# pokey-switch-board.net
KiCad netlist of a schematic drawn in Altium Designer
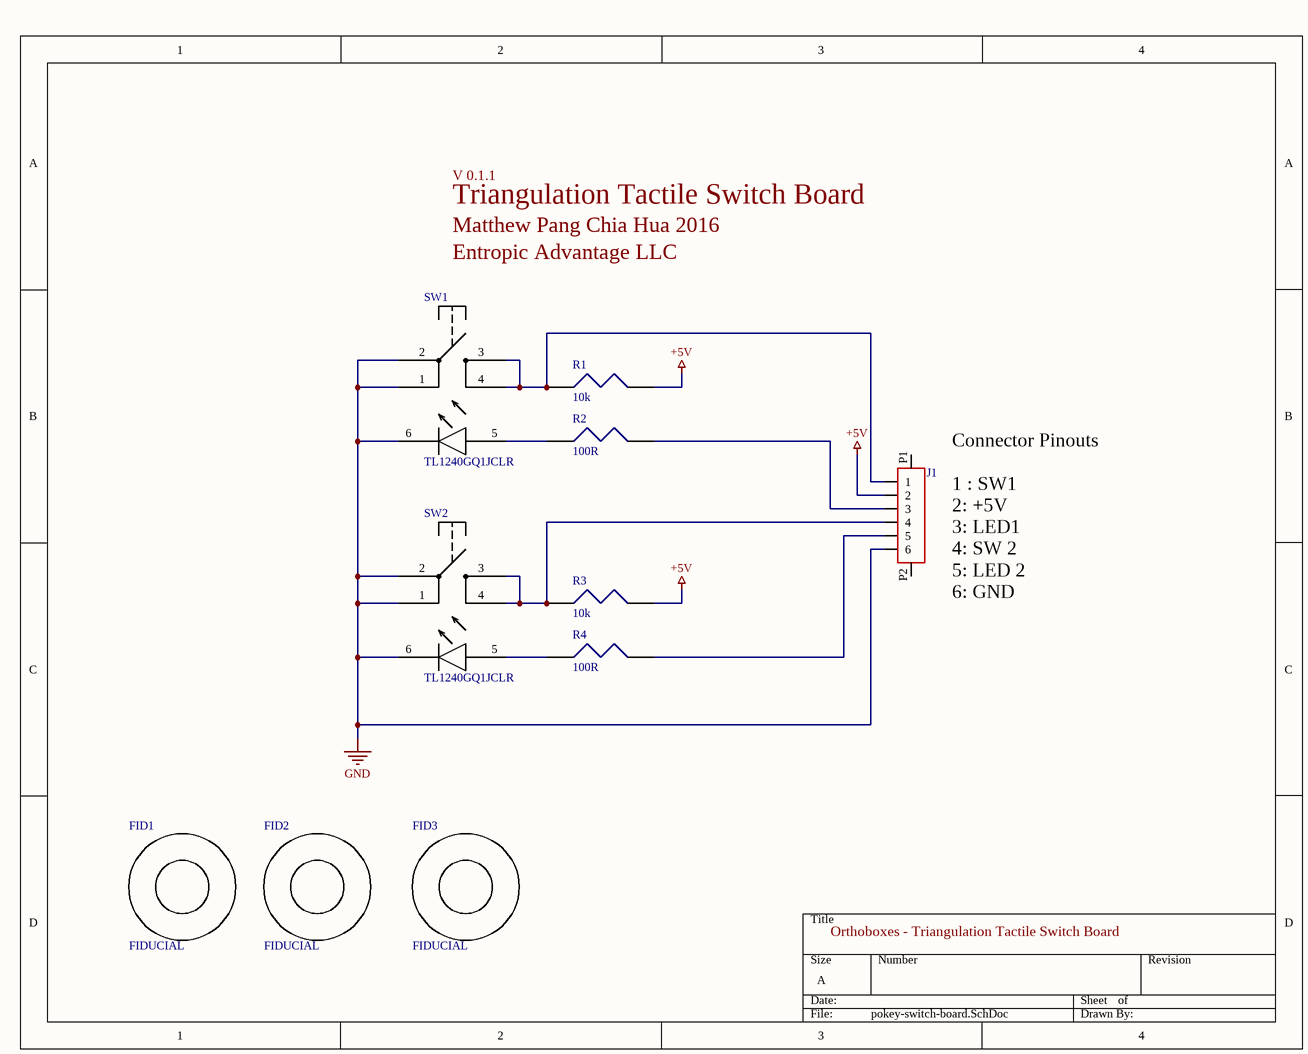
[diagram p0: pokey-switch-board.SchDoc]

(export (version "E")
  (design (tool "Eeschema 10.0.6"))
  (components
    (comp (ref "FID1")
      (value "FIDUCIAL")
      (footprint "pokey-switch-board:FID")
      (libsource (lib "pokey-switch-board") (part "Fiducial 1"))
    )
    (comp (ref "FID2")
      (value "FIDUCIAL")
      (footprint "pokey-switch-board:FID")
      (libsource (lib "pokey-switch-board") (part "Fiducial 1"))
    )
    (comp (ref "FID3")
      (value "FIDUCIAL")
      (footprint "pokey-switch-board:FID")
      (libsource (lib "pokey-switch-board") (part "Fiducial 1"))
    )
    (comp (ref "J1")
      (value "5034800600")
      (footprint "MOLEX 503480-0600")
      (description "CONN FFC FPC 6POS 0.50MM R/A")
      (fields (field (name "MANUFACTURER") "Molex, LLC"))
      (libsource (lib "generic 32u4") (part "5034800600"))
    )
    (comp (ref "R1")
      (value "10k")
      (footprint "RESC2012X07N_SAMSUNG")
      (description "RES SMD 10K OHM 1% 1/8W 0805")
      (fields
        (field (name "MANUFACTURER") "Samsung Electro-Mechanics America, Inc.")
        (field (name "MANUFACTURER PART NUMBER") "RC2012F103CS")
      )
      (libsource (lib "generic 32u4") (part "RC2012F103CS"))
    )
    (comp (ref "R2")
      (value "100R")
      (footprint "RESC2012X07N_SAMSUNG")
      (description "RES SMD 100 OHM 1% 1/8W 0805")
      (fields
        (field (name "MANUFACTURER") "Samsung Electro-Mechanics America, Inc.")
        (field (name "MANUFACTURER PART NUMBER") "RC2012F101CS")
      )
      (libsource (lib "generic 32u4") (part "RC2012F101CS"))
    )
    (comp (ref "R3")
      (value "10k")
      (footprint "RESC2012X07N_SAMSUNG")
      (description "RES SMD 10K OHM 1% 1/8W 0805")
      (fields
        (field (name "MANUFACTURER") "Samsung Electro-Mechanics America, Inc.")
        (field (name "MANUFACTURER PART NUMBER") "RC2012F103CS")
      )
      (libsource (lib "generic 32u4") (part "RC2012F103CS"))
    )
    (comp (ref "R4")
      (value "100R")
      (footprint "RESC2012X07N_SAMSUNG")
      (description "RES SMD 100 OHM 1% 1/8W 0805")
      (fields
        (field (name "MANUFACTURER") "Samsung Electro-Mechanics America, Inc.")
        (field (name "MANUFACTURER PART NUMBER") "RC2012F101CS")
      )
      (libsource (lib "generic 32u4") (part "RC2012F101CS"))
    )
    (comp (ref "SW1")
      (value "TL1240GQ1JCLR")
      (footprint "TL1240")
      (description "SWITCH TACTILE SPST-NO 0.05A 12V")
      (fields (field (name "MANUFACTURER") "E-Switch"))
      (libsource (lib "pokey-switch-board") (part "TL1240GQ1JCLR"))
    )
    (comp (ref "SW2")
      (value "TL1240GQ1JCLR")
      (footprint "TL1240")
      (description "SWITCH TACTILE SPST-NO 0.05A 12V")
      (fields (field (name "MANUFACTURER") "E-Switch"))
      (libsource (lib "pokey-switch-board") (part "TL1240GQ1JCLR"))
    )
  )
  (nets
    (net (code "1") (name "+5V") (class "Default")
      (node (ref "J1") (pin "2") (pinfunction "2_2") (pintype "passive"))
      (node (ref "R1") (pin "2") (pinfunction "2_2") (pintype "passive"))
      (node (ref "R3") (pin "2") (pinfunction "2_2") (pintype "passive"))
    )
    (net (code "2") (name "GND") (class "Default")
      (node (ref "J1") (pin "6") (pinfunction "6_6") (pintype "passive"))
      (node (ref "SW1") (pin "1") (pinfunction "1_1") (pintype "passive"))
      (node (ref "SW1") (pin "2") (pinfunction "2_2") (pintype "passive"))
      (node (ref "SW1") (pin "6") (pinfunction "6_6") (pintype "passive"))
      (node (ref "SW2") (pin "1") (pinfunction "1_1") (pintype "passive"))
      (node (ref "SW2") (pin "2") (pinfunction "2_2") (pintype "passive"))
      (node (ref "SW2") (pin "6") (pinfunction "6_6") (pintype "passive"))
    )
    (net (code "3") (name "Net-(J1-Pad1)") (class "Default")
      (node (ref "J1") (pin "1") (pinfunction "1_1") (pintype "passive"))
      (node (ref "R1") (pin "1") (pinfunction "1_1") (pintype "passive"))
      (node (ref "SW1") (pin "3") (pinfunction "3_3") (pintype "passive"))
      (node (ref "SW1") (pin "4") (pinfunction "4_4") (pintype "passive"))
    )
    (net (code "4") (name "Net-(J1-Pad3)") (class "Default")
      (node (ref "J1") (pin "3") (pinfunction "3_3") (pintype "passive"))
      (node (ref "R2") (pin "2") (pinfunction "2_2") (pintype "passive"))
    )
    (net (code "5") (name "Net-(J1-Pad4)") (class "Default")
      (node (ref "J1") (pin "4") (pinfunction "4_4") (pintype "passive"))
      (node (ref "R3") (pin "1") (pinfunction "1_1") (pintype "passive"))
      (node (ref "SW2") (pin "3") (pinfunction "3_3") (pintype "passive"))
      (node (ref "SW2") (pin "4") (pinfunction "4_4") (pintype "passive"))
    )
    (net (code "6") (name "Net-(J1-Pad5)") (class "Default")
      (node (ref "J1") (pin "5") (pinfunction "5_5") (pintype "passive"))
      (node (ref "R4") (pin "2") (pinfunction "2_2") (pintype "passive"))
    )
    (net (code "7") (name "Net-(R2-Pad1)") (class "Default")
      (node (ref "R2") (pin "1") (pinfunction "1_1") (pintype "passive"))
      (node (ref "SW1") (pin "5") (pinfunction "5_5") (pintype "passive"))
    )
    (net (code "8") (name "Net-(R4-Pad1)") (class "Default")
      (node (ref "R4") (pin "1") (pinfunction "1_1") (pintype "passive"))
      (node (ref "SW2") (pin "5") (pinfunction "5_5") (pintype "passive"))
    )
    (net (code "9") (name "unconnected-(J1-PadP1)") (class "Default")
      (node (ref "J1") (pin "P1") (pinfunction "P1_P1") (pintype "passive"))
    )
    (net (code "10") (name "unconnected-(J1-PadP2)") (class "Default")
      (node (ref "J1") (pin "P2") (pinfunction "P2_P2") (pintype "passive"))
    )
  )
)
